# Sheet2.net
KiCad netlist of a schematic drawn in Altium Designer
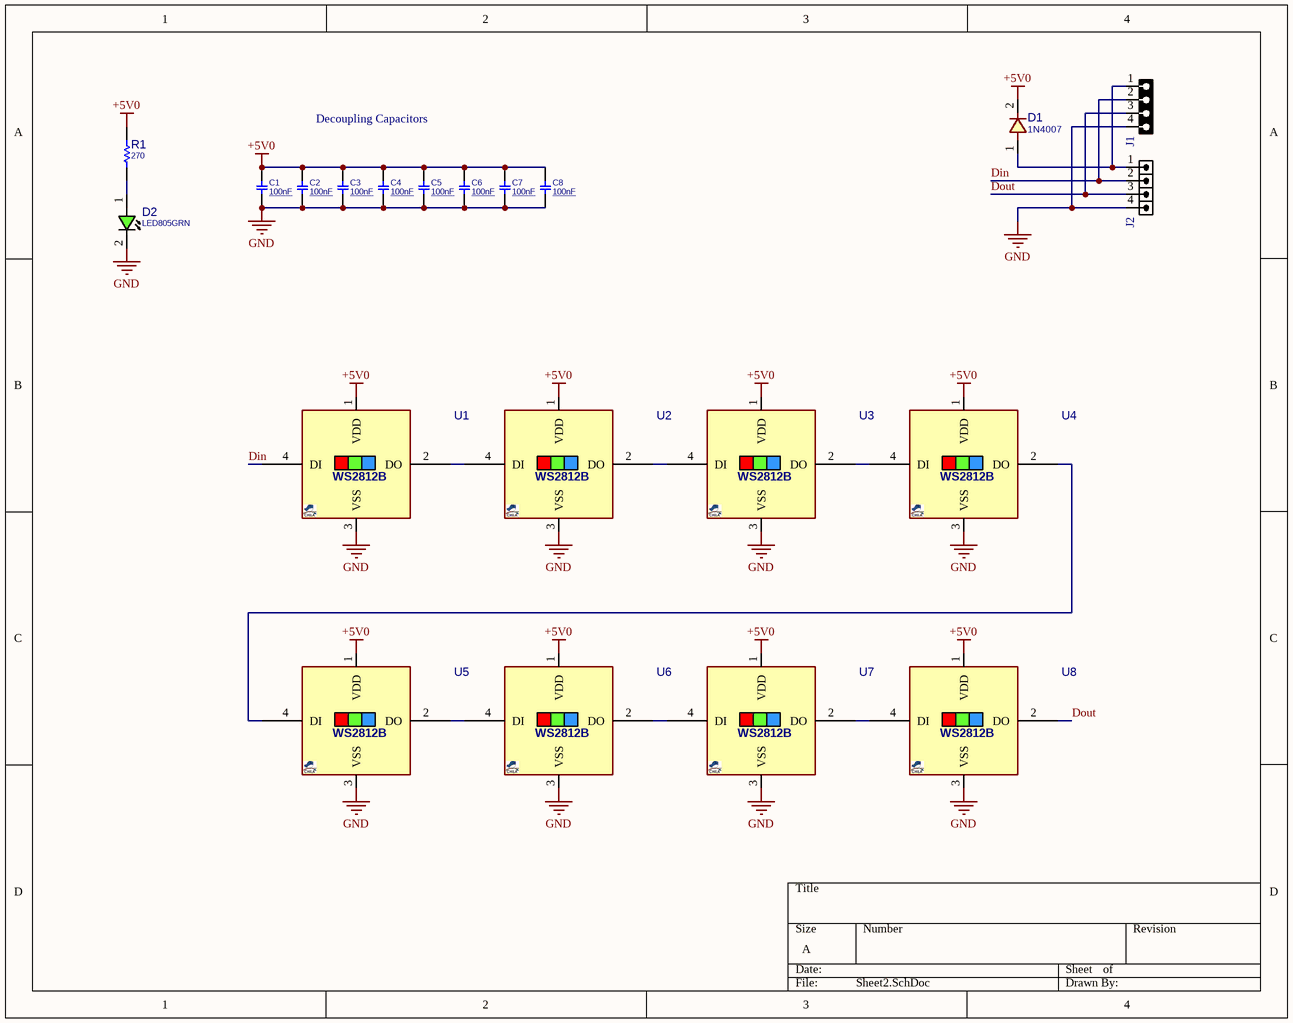
[diagram p0: Sheet2.SchDoc]

(export (version "E")
  (design (tool "Eeschema 10.0.6"))
  (components
    (comp (ref "C1")
      (value "100nF")
      (footprint "C0805")
      (description "CAP, MLCC, -F, -V, MATERIAL, -%, 0201")
      (fields (field (name "MANF_P#") "MANF_PART#"))
      (libsource (lib "passive_smd") (part "CAP_SMD_MLCC_0805"))
    )
    (comp (ref "C2")
      (value "100nF")
      (footprint "C0805")
      (description "CAP, MLCC, -F, -V, MATERIAL, -%, 0201")
      (fields (field (name "MANF_P#") "MANF_PART#"))
      (libsource (lib "passive_smd") (part "CAP_SMD_MLCC_0805"))
    )
    (comp (ref "C3")
      (value "100nF")
      (footprint "C0805")
      (description "CAP, MLCC, -F, -V, MATERIAL, -%, 0201")
      (fields (field (name "MANF_P#") "MANF_PART#"))
      (libsource (lib "passive_smd") (part "CAP_SMD_MLCC_0805"))
    )
    (comp (ref "C4")
      (value "100nF")
      (footprint "C0805")
      (description "CAP, MLCC, -F, -V, MATERIAL, -%, 0201")
      (fields (field (name "MANF_P#") "MANF_PART#"))
      (libsource (lib "passive_smd") (part "CAP_SMD_MLCC_0805"))
    )
    (comp (ref "C5")
      (value "100nF")
      (footprint "C0805")
      (description "CAP, MLCC, -F, -V, MATERIAL, -%, 0201")
      (fields (field (name "MANF_P#") "MANF_PART#"))
      (libsource (lib "passive_smd") (part "CAP_SMD_MLCC_0805"))
    )
    (comp (ref "C6")
      (value "100nF")
      (footprint "C0805")
      (description "CAP, MLCC, -F, -V, MATERIAL, -%, 0201")
      (fields (field (name "MANF_P#") "MANF_PART#"))
      (libsource (lib "passive_smd") (part "CAP_SMD_MLCC_0805"))
    )
    (comp (ref "C7")
      (value "100nF")
      (footprint "C0805")
      (description "CAP, MLCC, -F, -V, MATERIAL, -%, 0201")
      (fields (field (name "MANF_P#") "MANF_PART#"))
      (libsource (lib "passive_smd") (part "CAP_SMD_MLCC_0805"))
    )
    (comp (ref "C8")
      (value "100nF")
      (footprint "C0805")
      (description "CAP, MLCC, -F, -V, MATERIAL, -%, 0201")
      (fields (field (name "MANF_P#") "MANF_PART#"))
      (libsource (lib "passive_smd") (part "CAP_SMD_MLCC_0805"))
    )
    (comp (ref "D1")
      (value "1N4007")
      (footprint "D_SMA")
      (description "DIODE, GENERAL PURPOSE, 1000V/1A")
      (fields (field (name "MANF") "Kingtronics") (field (name "MANF_P#") "M7"))
      (libsource (lib "diode") (part "DIODE_SMD_1N4007"))
    )
    (comp (ref "D2")
      (value "LED805GRN")
      (footprint "LED0805GRN")
      (description "LED, SMD, 0805, GREEN")
      (libsource (lib "led(diode)") (part "LED_SMD_0805_GRN"))
    )
    (comp (ref "J1")
      (value "HDRF4")
      (footprint "HDR_F_1X4")
      (description "CONN, HEADER, Female, pitch: 2.54mm, 4POS")
      (libsource (lib "conn_header_2.54_st") (part "HDR_F_1X4"))
    )
    (comp (ref "J2")
      (value "HDR1X4")
      (footprint "HDR_M_1X4")
      (description "CONN, HEADER, Male, pitch: 2.54mm, 4POS")
      (libsource (lib "conn_header_2.54_st") (part "HDR_M_1X4"))
    )
    (comp (ref "R1")
      (value "270")
      (footprint "R0805")
      (description "RESISTOR, SMD")
      (libsource (lib "passive_smd") (part "RES_SMD"))
    )
    (comp (ref "U1")
      (value "WS2812B-B")
      (footprint "LED5050RGB_4")
      (description "LED, SMD, RGB with WS2812 4Lead")
      (fields (field (name "MANF") "Worldsemi"))
      (libsource (lib "led(diode)") (part "WS2812B-B_5050_4L"))
    )
    (comp (ref "U2")
      (value "WS2812B-B")
      (footprint "LED5050RGB_4")
      (description "LED, SMD, RGB with WS2812 4Lead")
      (fields (field (name "MANF") "Worldsemi"))
      (libsource (lib "led(diode)") (part "WS2812B-B_5050_4L"))
    )
    (comp (ref "U3")
      (value "WS2812B-B")
      (footprint "LED5050RGB_4")
      (description "LED, SMD, RGB with WS2812 4Lead")
      (fields (field (name "MANF") "Worldsemi"))
      (libsource (lib "led(diode)") (part "WS2812B-B_5050_4L"))
    )
    (comp (ref "U4")
      (value "WS2812B-B")
      (footprint "LED5050RGB_4")
      (description "LED, SMD, RGB with WS2812 4Lead")
      (fields (field (name "MANF") "Worldsemi"))
      (libsource (lib "led(diode)") (part "WS2812B-B_5050_4L"))
    )
    (comp (ref "U5")
      (value "WS2812B-B")
      (footprint "LED5050RGB_4")
      (description "LED, SMD, RGB with WS2812 4Lead")
      (fields (field (name "MANF") "Worldsemi"))
      (libsource (lib "led(diode)") (part "WS2812B-B_5050_4L"))
    )
    (comp (ref "U6")
      (value "WS2812B-B")
      (footprint "LED5050RGB_4")
      (description "LED, SMD, RGB with WS2812 4Lead")
      (fields (field (name "MANF") "Worldsemi"))
      (libsource (lib "led(diode)") (part "WS2812B-B_5050_4L"))
    )
    (comp (ref "U7")
      (value "WS2812B-B")
      (footprint "LED5050RGB_4")
      (description "LED, SMD, RGB with WS2812 4Lead")
      (fields (field (name "MANF") "Worldsemi"))
      (libsource (lib "led(diode)") (part "WS2812B-B_5050_4L"))
    )
    (comp (ref "U8")
      (value "WS2812B-B")
      (footprint "LED5050RGB_4")
      (description "LED, SMD, RGB with WS2812 4Lead")
      (fields (field (name "MANF") "Worldsemi"))
      (libsource (lib "led(diode)") (part "WS2812B-B_5050_4L"))
    )
  )
  (nets
    (net (code "1") (name "+5V0") (class "Default")
      (node (ref "C1") (pin "1") (pinfunction "1_1") (pintype "passive"))
      (node (ref "C2") (pin "1") (pinfunction "1_1") (pintype "passive"))
      (node (ref "C3") (pin "1") (pinfunction "1_1") (pintype "passive"))
      (node (ref "C4") (pin "1") (pinfunction "1_1") (pintype "passive"))
      (node (ref "C5") (pin "1") (pinfunction "1_1") (pintype "passive"))
      (node (ref "C6") (pin "1") (pinfunction "1_1") (pintype "passive"))
      (node (ref "C7") (pin "1") (pinfunction "1_1") (pintype "passive"))
      (node (ref "C8") (pin "1") (pinfunction "1_1") (pintype "passive"))
      (node (ref "D1") (pin "2") (pinfunction "2_2") (pintype "passive"))
      (node (ref "R1") (pin "2") (pinfunction "2_2") (pintype "passive"))
      (node (ref "U1") (pin "1") (pinfunction "VDD_1") (pintype "passive"))
      (node (ref "U2") (pin "1") (pinfunction "VDD_1") (pintype "passive"))
      (node (ref "U3") (pin "1") (pinfunction "VDD_1") (pintype "passive"))
      (node (ref "U4") (pin "1") (pinfunction "VDD_1") (pintype "passive"))
      (node (ref "U5") (pin "1") (pinfunction "VDD_1") (pintype "passive"))
      (node (ref "U6") (pin "1") (pinfunction "VDD_1") (pintype "passive"))
      (node (ref "U7") (pin "1") (pinfunction "VDD_1") (pintype "passive"))
      (node (ref "U8") (pin "1") (pinfunction "VDD_1") (pintype "passive"))
    )
    (net (code "2") (name "/Din") (class "Default")
      (node (ref "J1") (pin "2") (pinfunction "2_2") (pintype "passive"))
      (node (ref "J2") (pin "2") (pinfunction "2_2") (pintype "passive"))
      (node (ref "U1") (pin "4") (pinfunction "DI_4") (pintype "passive"))
    )
    (net (code "3") (name "/Dout") (class "Default")
      (node (ref "J1") (pin "3") (pinfunction "3_3") (pintype "passive"))
      (node (ref "J2") (pin "3") (pinfunction "3_3") (pintype "passive"))
      (node (ref "U8") (pin "2") (pinfunction "DO_2") (pintype "passive"))
    )
    (net (code "4") (name "GND") (class "Default")
      (node (ref "C1") (pin "2") (pinfunction "2_2") (pintype "passive"))
      (node (ref "C2") (pin "2") (pinfunction "2_2") (pintype "passive"))
      (node (ref "C3") (pin "2") (pinfunction "2_2") (pintype "passive"))
      (node (ref "C4") (pin "2") (pinfunction "2_2") (pintype "passive"))
      (node (ref "C5") (pin "2") (pinfunction "2_2") (pintype "passive"))
      (node (ref "C6") (pin "2") (pinfunction "2_2") (pintype "passive"))
      (node (ref "C7") (pin "2") (pinfunction "2_2") (pintype "passive"))
      (node (ref "C8") (pin "2") (pinfunction "2_2") (pintype "passive"))
      (node (ref "D2") (pin "2") (pinfunction "CATHODE_2") (pintype "passive"))
      (node (ref "J1") (pin "4") (pinfunction "4_4") (pintype "passive"))
      (node (ref "J2") (pin "4") (pinfunction "4_4") (pintype "passive"))
      (node (ref "U1") (pin "3") (pinfunction "VSS_3") (pintype "passive"))
      (node (ref "U2") (pin "3") (pinfunction "VSS_3") (pintype "passive"))
      (node (ref "U3") (pin "3") (pinfunction "VSS_3") (pintype "passive"))
      (node (ref "U4") (pin "3") (pinfunction "VSS_3") (pintype "passive"))
      (node (ref "U5") (pin "3") (pinfunction "VSS_3") (pintype "passive"))
      (node (ref "U6") (pin "3") (pinfunction "VSS_3") (pintype "passive"))
      (node (ref "U7") (pin "3") (pinfunction "VSS_3") (pintype "passive"))
      (node (ref "U8") (pin "3") (pinfunction "VSS_3") (pintype "passive"))
    )
    (net (code "5") (name "Net-(D1-Pad1)") (class "Default")
      (node (ref "D1") (pin "1") (pinfunction "1_1") (pintype "passive"))
      (node (ref "J1") (pin "1") (pinfunction "1_1") (pintype "passive"))
      (node (ref "J2") (pin "1") (pinfunction "1_1") (pintype "passive"))
    )
    (net (code "6") (name "Net-(D2-ANODE)") (class "Default")
      (node (ref "D2") (pin "1") (pinfunction "ANODE_1") (pintype "passive"))
      (node (ref "R1") (pin "1") (pinfunction "1_1") (pintype "passive"))
    )
    (net (code "7") (name "Net-(U1-DO)") (class "Default")
      (node (ref "U1") (pin "2") (pinfunction "DO_2") (pintype "passive"))
      (node (ref "U2") (pin "4") (pinfunction "DI_4") (pintype "passive"))
    )
    (net (code "8") (name "Net-(U2-DO)") (class "Default")
      (node (ref "U2") (pin "2") (pinfunction "DO_2") (pintype "passive"))
      (node (ref "U3") (pin "4") (pinfunction "DI_4") (pintype "passive"))
    )
    (net (code "9") (name "Net-(U3-DO)") (class "Default")
      (node (ref "U3") (pin "2") (pinfunction "DO_2") (pintype "passive"))
      (node (ref "U4") (pin "4") (pinfunction "DI_4") (pintype "passive"))
    )
    (net (code "10") (name "Net-(U4-DO)") (class "Default")
      (node (ref "U4") (pin "2") (pinfunction "DO_2") (pintype "passive"))
      (node (ref "U5") (pin "4") (pinfunction "DI_4") (pintype "passive"))
    )
    (net (code "11") (name "Net-(U5-DO)") (class "Default")
      (node (ref "U5") (pin "2") (pinfunction "DO_2") (pintype "passive"))
      (node (ref "U6") (pin "4") (pinfunction "DI_4") (pintype "passive"))
    )
    (net (code "12") (name "Net-(U6-DO)") (class "Default")
      (node (ref "U6") (pin "2") (pinfunction "DO_2") (pintype "passive"))
      (node (ref "U7") (pin "4") (pinfunction "DI_4") (pintype "passive"))
    )
    (net (code "13") (name "Net-(U7-DO)") (class "Default")
      (node (ref "U7") (pin "2") (pinfunction "DO_2") (pintype "passive"))
      (node (ref "U8") (pin "4") (pinfunction "DI_4") (pintype "passive"))
    )
  )
)
